# top-level.net
KiCad netlist of a schematic drawn in Altium Designer
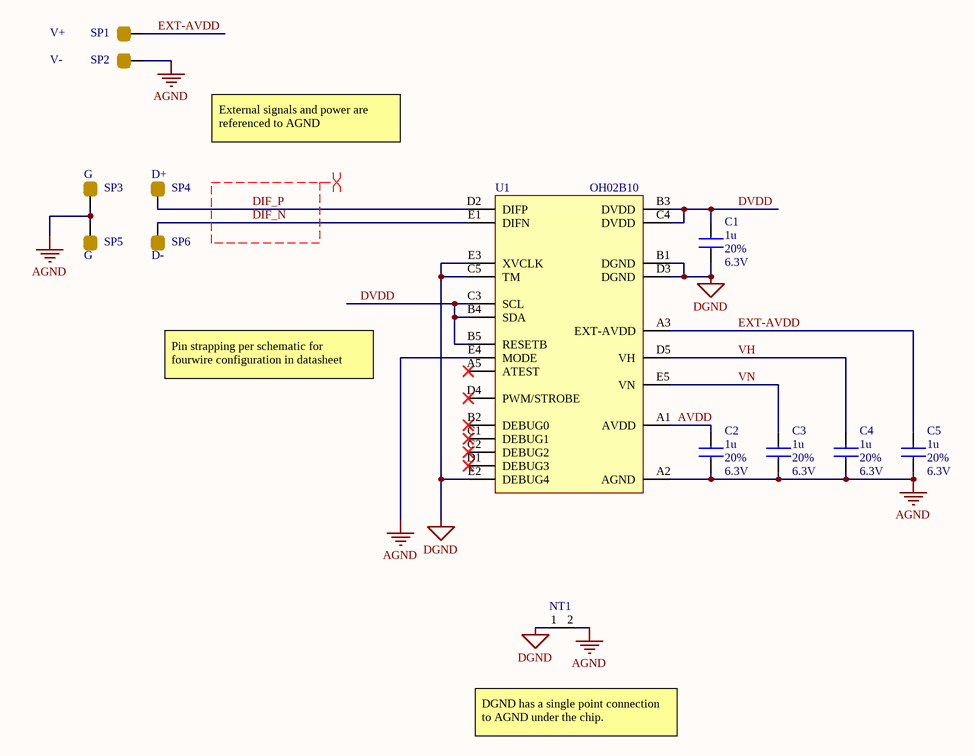
[diagram p0: top-level.SchDoc]

(export (version "E")
  (design (tool "Eeschema 10.0.6"))
  (components
    (comp (ref "C1")
      (value "1u")
      (footprint "CAPC0603X04L")
      (description "CAP CER 1UF 6.3V X7T 0201")
      (fields
        (field (name "TOLERANCE") "20%")
        (field (name "RATING") "6.3V")
        (field (name "Comment") "GRT033D70J105ME13D")
      )
      (libsource (lib "Cove Technology Consulting, LLC") (part "CAP_NONPOL"))
    )
    (comp (ref "C2")
      (value "1u")
      (footprint "CAPC0603X04L")
      (description "CAP CER 1UF 6.3V X7T 0201")
      (fields
        (field (name "TOLERANCE") "20%")
        (field (name "RATING") "6.3V")
        (field (name "Comment") "GRT033D70J105ME13D")
      )
      (libsource (lib "Cove Technology Consulting, LLC") (part "CAP_NONPOL"))
    )
    (comp (ref "C3")
      (value "1u")
      (footprint "CAPC0603X04L")
      (description "CAP CER 1UF 6.3V X7T 0201")
      (fields
        (field (name "TOLERANCE") "20%")
        (field (name "RATING") "6.3V")
        (field (name "Comment") "GRT033D70J105ME13D")
      )
      (libsource (lib "Cove Technology Consulting, LLC") (part "CAP_NONPOL"))
    )
    (comp (ref "C4")
      (value "1u")
      (footprint "CAPC0603X04L")
      (description "CAP CER 1UF 6.3V X7T 0201")
      (fields
        (field (name "TOLERANCE") "20%")
        (field (name "RATING") "6.3V")
        (field (name "Comment") "GRT033D70J105ME13D")
      )
      (libsource (lib "Cove Technology Consulting, LLC") (part "CAP_NONPOL"))
    )
    (comp (ref "C5")
      (value "1u")
      (footprint "CAPC0603X04L")
      (description "CAP CER 1UF 6.3V X7T 0201")
      (fields
        (field (name "TOLERANCE") "20%")
        (field (name "RATING") "6.3V")
        (field (name "Comment") "GRT033D70J105ME13D")
      )
      (libsource (lib "Cove Technology Consulting, LLC") (part "CAP_NONPOL"))
    )
    (comp (ref "NT1")
      (value "NET_TIE")
      (footprint "NET_TIE_0.15X0.45MM")
      (libsource (lib "Cove Technology Consulting, LLC") (part "NET_TIE"))
    )
    (comp (ref "SP1")
      (value "V+")
      (footprint "SP-0.4x0.4mm")
      (description "Solder Pad")
      (libsource (lib "Cove Technology Consulting, LLC") (part "SP"))
    )
    (comp (ref "SP2")
      (value "V-")
      (footprint "SP-0.4x0.4mm")
      (description "Solder Pad")
      (libsource (lib "Cove Technology Consulting, LLC") (part "SP"))
    )
    (comp (ref "SP3")
      (value "G")
      (footprint "SP-0.6x0.6mm")
      (description "Solder Pad")
      (libsource (lib "Cove Technology Consulting, LLC") (part "SP"))
    )
    (comp (ref "SP4")
      (value "D+")
      (footprint "SP-0.4x0.4mm")
      (description "Solder Pad")
      (libsource (lib "Cove Technology Consulting, LLC") (part "SP"))
    )
    (comp (ref "SP5")
      (value "G")
      (footprint "SP-0.6x0.6mm")
      (description "Solder Pad")
      (libsource (lib "Cove Technology Consulting, LLC") (part "SP"))
    )
    (comp (ref "SP6")
      (value "D-")
      (footprint "SP-0.4x0.4mm")
      (description "Solder Pad")
      (libsource (lib "Cove Technology Consulting, LLC") (part "SP"))
    )
    (comp (ref "U1")
      (value "OH02B10")
      (footprint "BGA24C40P5X5_249X249X52")
      (description "CMOS Image Sensor, Color, 2MP, 1500x1500, 1/7.5\"")
      (libsource (lib "Cove Technology Consulting, LLC") (part "OMNIVISION-OH02B10-A24A-001A"))
    )
  )
  (nets
    (net (code "1") (name "/AVDD") (class "Default")
      (node (ref "C2") (pin "1") (pinfunction "1_1") (pintype "passive"))
      (node (ref "U1") (pin "A1") (pinfunction "AVDD_A1") (pintype "passive"))
    )
    (net (code "2") (name "/DIF_N") (class "Default")
      (node (ref "SP6") (pin "1") (pinfunction "TP_1") (pintype "passive"))
      (node (ref "U1") (pin "E1") (pinfunction "DIFN_E1") (pintype "passive"))
    )
    (net (code "3") (name "/DIF_P") (class "Default")
      (node (ref "SP4") (pin "1") (pinfunction "TP_1") (pintype "passive"))
      (node (ref "U1") (pin "D2") (pinfunction "DIFP_D2") (pintype "passive"))
    )
    (net (code "4") (name "/DVDD") (class "Default")
      (node (ref "C1") (pin "1") (pinfunction "1_1") (pintype "passive"))
      (node (ref "U1") (pin "B3") (pinfunction "DVDD_B3") (pintype "passive"))
      (node (ref "U1") (pin "B4") (pinfunction "SDA_B4") (pintype "passive"))
      (node (ref "U1") (pin "B5") (pinfunction "RESETB_B5") (pintype "passive"))
      (node (ref "U1") (pin "C3") (pinfunction "SCL_C3") (pintype "passive"))
      (node (ref "U1") (pin "C4") (pinfunction "DVDD_C4") (pintype "passive"))
    )
    (net (code "5") (name "/EXT-AVDD") (class "Default")
      (node (ref "C5") (pin "1") (pinfunction "1_1") (pintype "passive"))
      (node (ref "SP1") (pin "1") (pinfunction "TP_1") (pintype "passive"))
      (node (ref "U1") (pin "A3") (pinfunction "EXT-AVDD_A3") (pintype "passive"))
    )
    (net (code "6") (name "/VH") (class "Default")
      (node (ref "C4") (pin "1") (pinfunction "1_1") (pintype "passive"))
      (node (ref "U1") (pin "D5") (pinfunction "VH_D5") (pintype "passive"))
    )
    (net (code "7") (name "/VN") (class "Default")
      (node (ref "C3") (pin "1") (pinfunction "1_1") (pintype "passive"))
      (node (ref "U1") (pin "E5") (pinfunction "VN_E5") (pintype "passive"))
    )
    (net (code "8") (name "AGND") (class "Default")
      (node (ref "C2") (pin "2") (pinfunction "2_2") (pintype "passive"))
      (node (ref "C3") (pin "2") (pinfunction "2_2") (pintype "passive"))
      (node (ref "C4") (pin "2") (pinfunction "2_2") (pintype "passive"))
      (node (ref "C5") (pin "2") (pinfunction "2_2") (pintype "passive"))
      (node (ref "NT1") (pin "2") (pinfunction "2_2") (pintype "passive"))
      (node (ref "SP2") (pin "1") (pinfunction "TP_1") (pintype "passive"))
      (node (ref "SP3") (pin "1") (pinfunction "TP_1") (pintype "passive"))
      (node (ref "SP5") (pin "1") (pinfunction "TP_1") (pintype "passive"))
      (node (ref "U1") (pin "A2") (pinfunction "AGND_A2") (pintype "passive"))
      (node (ref "U1") (pin "E4") (pinfunction "MODE_E4") (pintype "passive"))
    )
    (net (code "9") (name "DGND") (class "Default")
      (node (ref "C1") (pin "2") (pinfunction "2_2") (pintype "passive"))
      (node (ref "NT1") (pin "1") (pinfunction "1_1") (pintype "passive"))
      (node (ref "U1") (pin "B1") (pinfunction "DGND_B1") (pintype "passive"))
      (node (ref "U1") (pin "C5") (pinfunction "TM_C5") (pintype "passive"))
      (node (ref "U1") (pin "D3") (pinfunction "DGND_D3") (pintype "passive"))
      (node (ref "U1") (pin "E2") (pinfunction "DEBUG4_E2") (pintype "passive"))
      (node (ref "U1") (pin "E3") (pinfunction "XVCLK_E3") (pintype "passive"))
    )
    (net (code "10") (name "unconnected-(U1-ATEST-PadA5)") (class "Default")
      (node (ref "U1") (pin "A5") (pinfunction "ATEST_A5") (pintype "passive+no_connect"))
    )
    (net (code "11") (name "unconnected-(U1-DEBUG0-PadB2)") (class "Default")
      (node (ref "U1") (pin "B2") (pinfunction "DEBUG0_B2") (pintype "passive+no_connect"))
    )
    (net (code "12") (name "unconnected-(U1-DEBUG1-PadC1)") (class "Default")
      (node (ref "U1") (pin "C1") (pinfunction "DEBUG1_C1") (pintype "passive+no_connect"))
    )
    (net (code "13") (name "unconnected-(U1-DEBUG2-PadC2)") (class "Default")
      (node (ref "U1") (pin "C2") (pinfunction "DEBUG2_C2") (pintype "passive+no_connect"))
    )
    (net (code "14") (name "unconnected-(U1-DEBUG3-PadD1)") (class "Default")
      (node (ref "U1") (pin "D1") (pinfunction "DEBUG3_D1") (pintype "passive+no_connect"))
    )
    (net (code "15") (name "unconnected-(U1-PWM{slash}STROBE-PadD4)") (class "Default")
      (node (ref "U1") (pin "D4") (pinfunction "PWM/STROBE_D4") (pintype "passive+no_connect"))
    )
  )
)
